# MCU_M_V2.net
KiCad netlist of a schematic drawn in Altium Designer
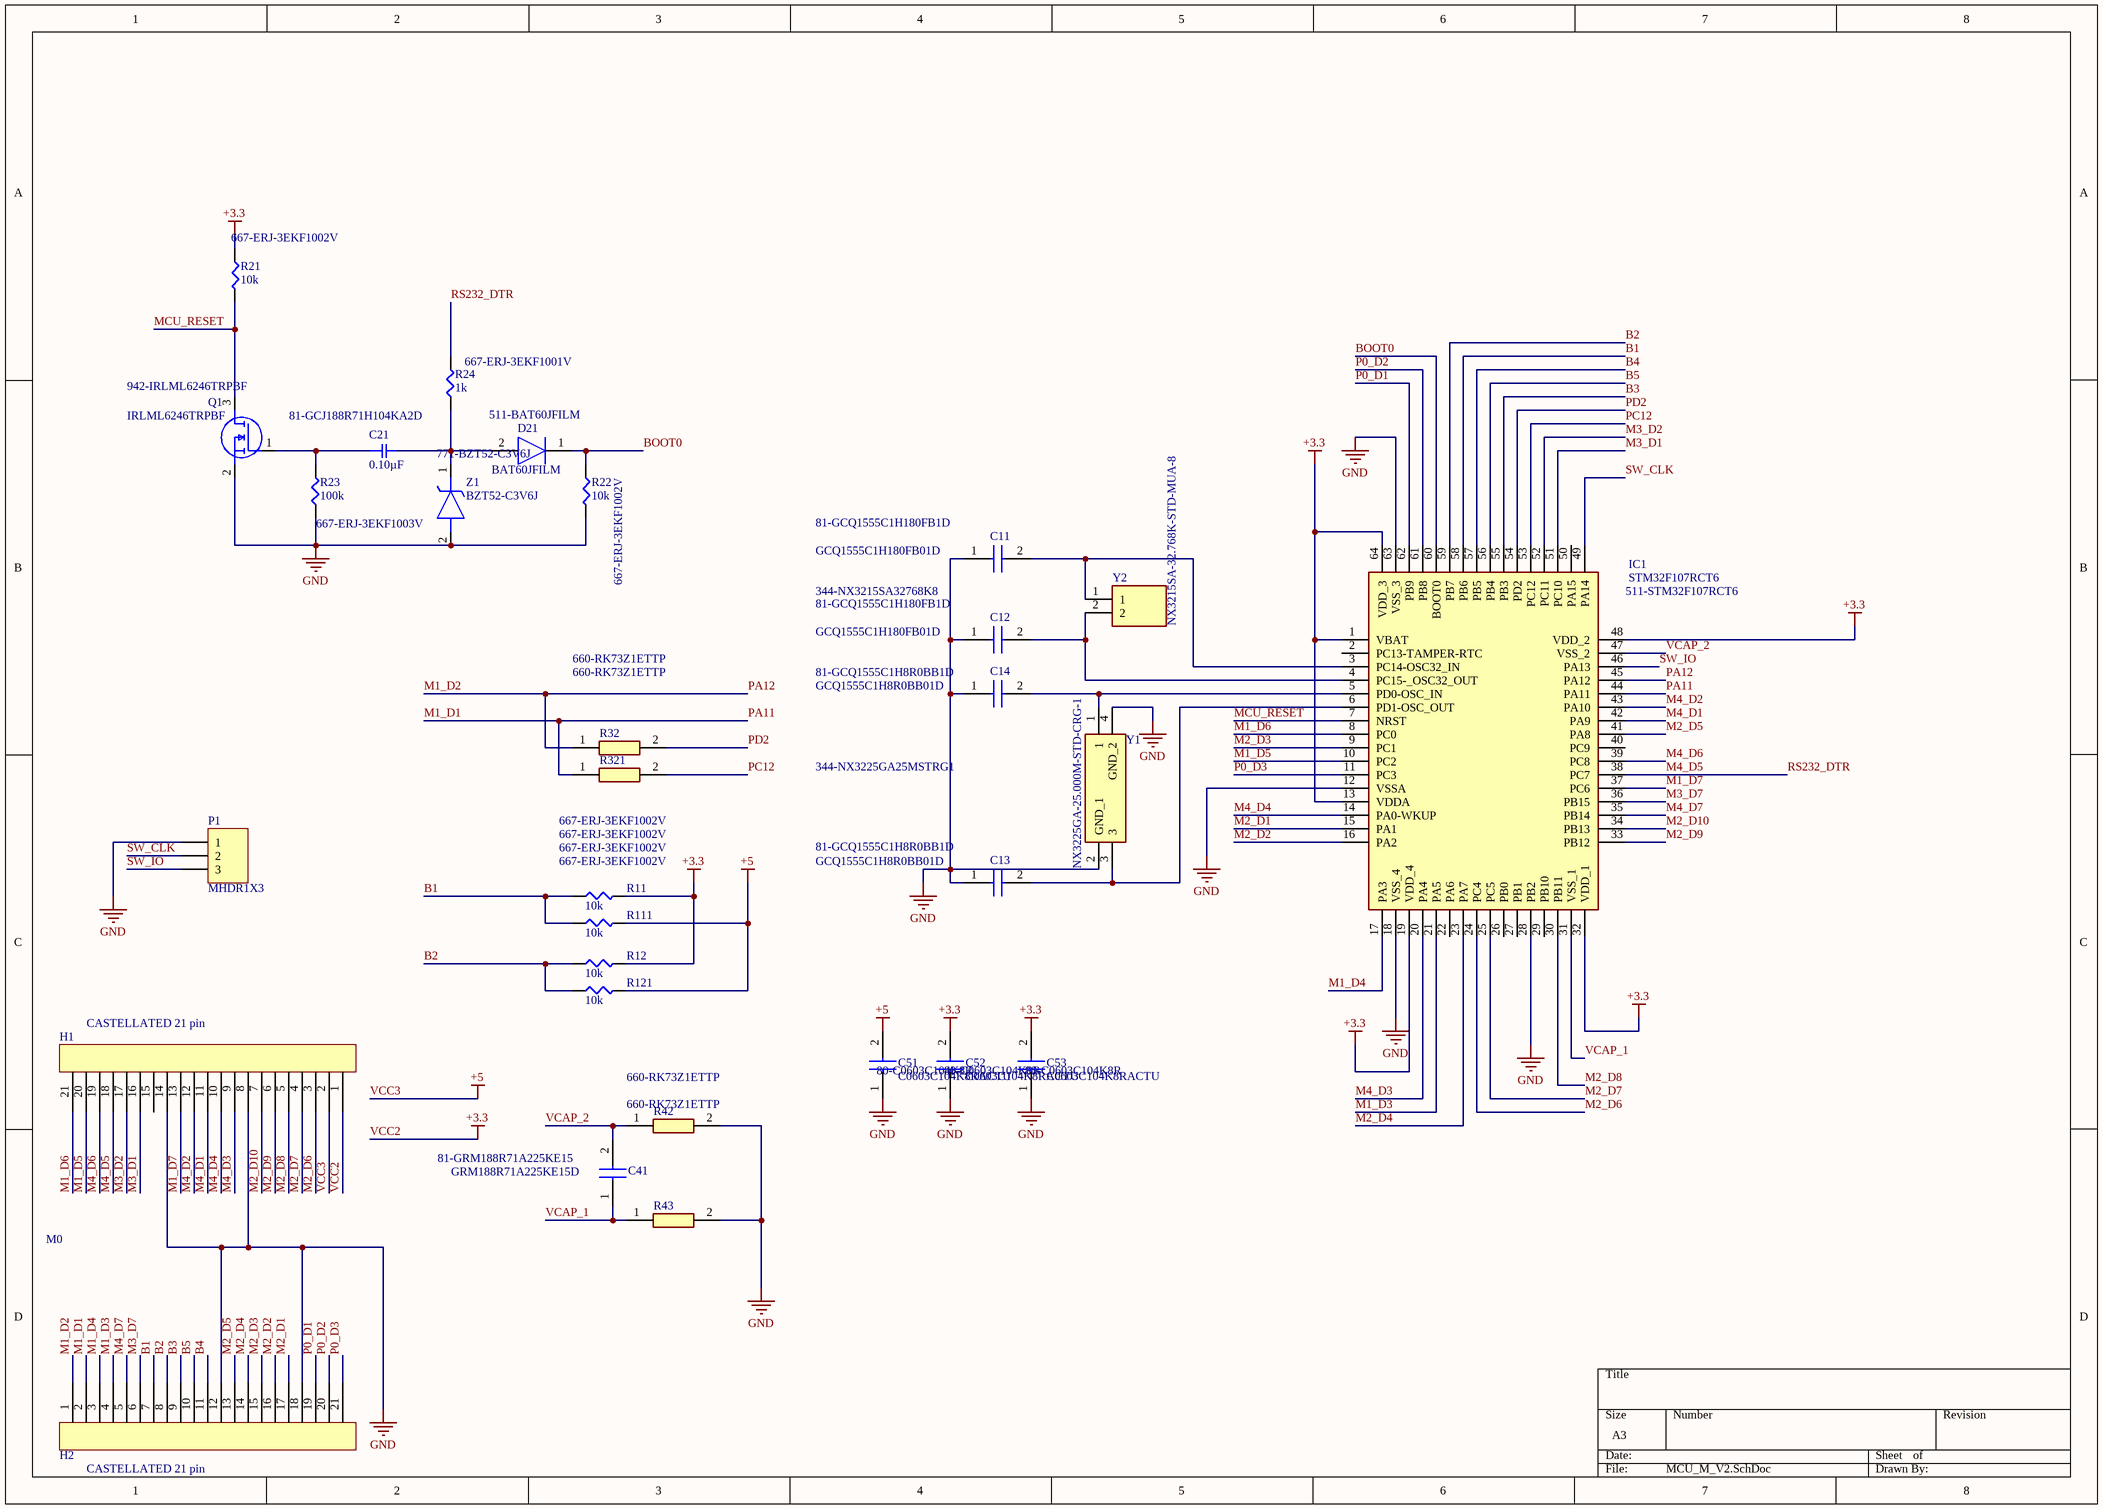
[diagram p0: MCU_M_V2.SchDoc]

(export (version "E")
  (design (tool "Eeschema 10.0.6"))
  (components
    (comp (ref "C11")
      (value "GCQ1555C1H180FB01D")
      (footprint "SamacSys:CAPC1005X55N")
      (description "Capacitor")
      (fields (field (name "SUPPLIER PART NUMBER 1") "81-GCQ1555C1H180FB1D"))
      (libsource (lib "*") (part "GCQ1555C1H180FB01D"))
    )
    (comp (ref "C12")
      (value "GCQ1555C1H180FB01D")
      (footprint "SamacSys:CAPC1005X55N")
      (description "Capacitor")
      (fields (field (name "SUPPLIER PART NUMBER 1") "81-GCQ1555C1H180FB1D"))
      (libsource (lib "*") (part "GCQ1555C1H180FB01D"))
    )
    (comp (ref "C13")
      (value "GCQ1555C1H8R0BB01D")
      (footprint "SamacSys:CAPC1005X55N")
      (description "Capacitor")
      (fields (field (name "SUPPLIER PART NUMBER 1") "81-GCQ1555C1H8R0BB1D"))
      (libsource (lib "*") (part "GCQ1555C1H8R0BB01D"))
    )
    (comp (ref "C14")
      (value "GCQ1555C1H8R0BB01D")
      (footprint "SamacSys:CAPC1005X55N")
      (description "Capacitor")
      (fields (field (name "SUPPLIER PART NUMBER 1") "81-GCQ1555C1H8R0BB1D"))
      (libsource (lib "*") (part "GCQ1555C1H8R0BB01D"))
    )
    (comp (ref "C21")
      (value "0.10µF")
      (footprint "SMD-0603C")
      (description "CAP CER 0.1UF 50V X7R 0603")
      (fields
        (field (name "DIGI-KEY PART NUMBER") "490-5798-1-ND")
        (field (name "PART NUMBER") "GCJ188R71H104KA12D")
        (field (name "SUPPLIER PART NUMBER 1") "81-GCJ188R71H104KA2D")
      )
      (libsource (lib "capacitor_murata_0603") (part "GCJ188R71H104KA12D"))
    )
    (comp (ref "C41")
      (value "GRM188R71A225KE15D")
      (footprint "SamacSys:CAPC1608X90N")
      (description "Capacitor")
      (fields (field (name "SUPPLIER PART NUMBER 1") "81-GRM188R71A225KE15"))
      (libsource (lib "*") (part "GRM188R71A225KE15D"))
    )
    (comp (ref "C51")
      (value "C0603C104K8RACTU")
      (footprint "SamacSys:CAPC1608X90N")
      (description "Capacitor")
      (fields (field (name "SUPPLIER PART NUMBER 1") "80-C0603C104K8R"))
      (libsource (lib "SamacSys") (part "C0603C104K8RACTU"))
    )
    (comp (ref "C52")
      (value "C0603C104K8RACTU")
      (footprint "SamacSys:CAPC1608X90N")
      (description "Capacitor")
      (fields (field (name "SUPPLIER PART NUMBER 1") "80-C0603C104K8R"))
      (libsource (lib "SamacSys") (part "C0603C104K8RACTU"))
    )
    (comp (ref "C53")
      (value "C0603C104K8RACTU")
      (footprint "SamacSys:CAPC1608X90N")
      (description "Capacitor")
      (fields (field (name "SUPPLIER PART NUMBER 1") "80-C0603C104K8R"))
      (libsource (lib "SamacSys") (part "C0603C104K8RACTU"))
    )
    (comp (ref "D21")
      (value "BAT60JFILM")
      (footprint "SamacSys:SOD2513X117N")
      (description "Diode")
      (fields
        (field (name "MOUSER2 PART NUMBER") "511-BAT60JFILM")
        (field (name "SUPPLIER PART NUMBER 1") "511-BAT60JFILM")
      )
      (libsource (lib "*") (part "BAT60JFILM"))
    )
    (comp (ref "H1")
      (value "CASTELLATED 21 pin")
      (footprint "CASTELLATED 21 pin")
      (libsource (lib "USIB") (part "CASTELLATED 21 pin"))
    )
    (comp (ref "H2")
      (value "CASTELLATED 21 pin")
      (footprint "CASTELLATED 21 pin")
      (libsource (lib "") (part "CASTELLATED 21 pin_1"))
    )
    (comp (ref "IC1")
      (value "STM32F107RCT6")
      (footprint "SamacSys:QFP50P1200X1200X160-64N")
      (description "Integrated Circuit")
      (fields
        (field (name "MOUSER2 PART NUMBER") "511-STM32F107RCT6")
        (field (name "SUPPLIER PART NUMBER 1") "511-STM32F107RCT6")
      )
      (libsource (lib "*") (part "STM32F107RCT6"))
    )
    (comp (ref "P1")
      (value "MHDR1X3")
      (footprint "MHDR1X3")
      (description "Header, 3-Pin")
      (fields (field (name "PUBLISHER") "Altium Limited"))
      (libsource (lib "Miscellaneous Connectors") (part "MHDR1X3"))
    )
    (comp (ref "Q1")
      (value "IRLML6246TRPBF")
      (footprint "SamacSys:SOT95P237X112-3N")
      (description "MOSFET (N-Channel)")
      (fields (field (name "SUPPLIER PART NUMBER 1") "942-IRLML6246TRPBF"))
      (libsource (lib "*") (part "IRLML6246TRPBF"))
    )
    (comp (ref "R11")
      (value "10k")
      (footprint "SMD-0603-RES")
      (description "RES SMD 10K OHM 1% 1/10W 0603")
      (fields
        (field (name "PART NUMBER") "ERJ-3EKF1002V")
        (field (name "DIGI-KEY PART NUMBER") "P10.0KHCT-ND")
        (field (name "SUPPLIER PART NUMBER 1") "667-ERJ-3EKF1002V")
      )
      (libsource (lib "Panasonic_ERJ_0603") (part "ERJ-3EKF1002V"))
    )
    (comp (ref "R12")
      (value "10k")
      (footprint "SMD-0603-RES")
      (description "RES SMD 10K OHM 1% 1/10W 0603")
      (fields
        (field (name "PART NUMBER") "ERJ-3EKF1002V")
        (field (name "DIGI-KEY PART NUMBER") "P10.0KHCT-ND")
        (field (name "SUPPLIER PART NUMBER 1") "667-ERJ-3EKF1002V")
      )
      (libsource (lib "Panasonic_ERJ_0603") (part "ERJ-3EKF1002V"))
    )
    (comp (ref "R21")
      (value "10k")
      (footprint "SMD-0603-RES")
      (description "RES SMD 10K OHM 1% 1/10W 0603")
      (fields
        (field (name "PART NUMBER") "ERJ-3EKF1002V")
        (field (name "DIGI-KEY PART NUMBER") "P10.0KHCT-ND")
        (field (name "SUPPLIER PART NUMBER 1") "667-ERJ-3EKF1002V")
      )
      (libsource (lib "Panasonic_ERJ_0603") (part "ERJ-3EKF1002V"))
    )
    (comp (ref "R22")
      (value "10k")
      (footprint "SMD-0603-RES")
      (description "RES SMD 10K OHM 1% 1/10W 0603")
      (fields
        (field (name "PART NUMBER") "ERJ-3EKF1002V")
        (field (name "DIGI-KEY PART NUMBER") "P10.0KHCT-ND")
        (field (name "SUPPLIER PART NUMBER 1") "667-ERJ-3EKF1002V")
      )
      (libsource (lib "Panasonic_ERJ_0603") (part "ERJ-3EKF1002V"))
    )
    (comp (ref "R23")
      (value "100k")
      (footprint "SMD-0603-RES")
      (description "RES SMD 100K OHM 1% 1/10W 0603")
      (fields
        (field (name "PART NUMBER") "ERJ-3EKF1003V")
        (field (name "DIGI-KEY PART NUMBER") "P100KHCT-ND")
        (field (name "SUPPLIER PART NUMBER 1") "667-ERJ-3EKF1003V")
      )
      (libsource (lib "Panasonic_ERJ_0603") (part "ERJ-3EKF1003V"))
    )
    (comp (ref "R24")
      (value "1k")
      (footprint "SMD-0603-RES")
      (description "RES SMD 1K OHM 1% 1/10W 0603")
      (fields
        (field (name "PART NUMBER") "ERJ-3EKF1001V")
        (field (name "DIGI-KEY PART NUMBER") "P1.00KHCT-ND")
        (field (name "SUPPLIER PART NUMBER 1") "667-ERJ-3EKF1001V")
      )
      (libsource (lib "Panasonic_ERJ_0603") (part "ERJ-3EKF1001V"))
    )
    (comp (ref "R32")
      (value "RK73Z1ETTP")
      (footprint "SamacSys:RESC1005X40N")
      (description "Resistor")
      (fields (field (name "SUPPLIER PART NUMBER 1") "660-RK73Z1ETTP"))
      (libsource (lib "SamacSys") (part "RK73Z1ETTP"))
    )
    (comp (ref "R42")
      (value "RK73Z1ETTP")
      (footprint "SamacSys:RESC1005X40N")
      (description "Resistor")
      (fields (field (name "SUPPLIER PART NUMBER 1") "660-RK73Z1ETTP"))
      (libsource (lib "SamacSys") (part "RK73Z1ETTP"))
    )
    (comp (ref "R43")
      (value "RK73Z1ETTP")
      (footprint "SamacSys:RESC1005X40N")
      (description "Resistor")
      (fields (field (name "SUPPLIER PART NUMBER 1") "660-RK73Z1ETTP"))
      (libsource (lib "SamacSys") (part "RK73Z1ETTP"))
    )
    (comp (ref "R111")
      (value "10k")
      (footprint "SMD-0603-RES")
      (description "RES SMD 10K OHM 1% 1/10W 0603")
      (fields
        (field (name "PART NUMBER") "ERJ-3EKF1002V")
        (field (name "DIGI-KEY PART NUMBER") "P10.0KHCT-ND")
        (field (name "SUPPLIER PART NUMBER 1") "667-ERJ-3EKF1002V")
      )
      (libsource (lib "Panasonic_ERJ_0603") (part "ERJ-3EKF1002V"))
    )
    (comp (ref "R121")
      (value "10k")
      (footprint "SMD-0603-RES")
      (description "RES SMD 10K OHM 1% 1/10W 0603")
      (fields
        (field (name "PART NUMBER") "ERJ-3EKF1002V")
        (field (name "DIGI-KEY PART NUMBER") "P10.0KHCT-ND")
        (field (name "SUPPLIER PART NUMBER 1") "667-ERJ-3EKF1002V")
      )
      (libsource (lib "Panasonic_ERJ_0603") (part "ERJ-3EKF1002V"))
    )
    (comp (ref "R321")
      (value "RK73Z1ETTP")
      (footprint "SamacSys:RESC1005X40N")
      (description "Resistor")
      (fields (field (name "SUPPLIER PART NUMBER 1") "660-RK73Z1ETTP"))
      (libsource (lib "SamacSys") (part "RK73Z1ETTP"))
    )
    (comp (ref "Y1")
      (value "NX3225GA-25.000M-STD-CRG-1")
      (footprint "SamacSys:NX3225SA_1")
      (description "Crystal or Oscillator")
      (fields
        (field (name "MOUSER2 PART NUMBER") "344-NX3225GA25MSTRG1")
        (field (name "SUPPLIER PART NUMBER 1") "344-NX3225GA25MSTRG1")
      )
      (libsource (lib "*") (part "NX3225GA-25.000M-STD-CRG-1"))
    )
    (comp (ref "Y2")
      (value "NX3215SA-32.768K-STD-MUA-8")
      (footprint "SamacSys:NX3215SA")
      (description "Crystal or Oscillator")
      (fields
        (field (name "MOUSER2 PART NUMBER") "344-NX3215SA32768K8")
        (field (name "SUPPLIER PART NUMBER 1") "344-NX3215SA32768K8")
      )
      (libsource (lib "*") (part "NX3215SA-32.768K-STD-MUA-8"))
    )
    (comp (ref "Z1")
      (value "BZT52-C3V6J")
      (footprint "SamacSys:SOD123")
      (description "Zener Diode")
      (fields
        (field (name "MOUSER2 PART NUMBER") "771-BZT52-C3V6J")
        (field (name "SUPPLIER PART NUMBER 1") "771-BZT52-C3V6J")
      )
      (libsource (lib "*") (part "BZT52-C3V6J"))
    )
  )
  (nets
    (net (code "1") (name "+3.3") (class "Default")
      (node (ref "C52") (pin "2") (pinfunction "2_2") (pintype "passive"))
      (node (ref "C53") (pin "2") (pinfunction "2_2") (pintype "passive"))
      (node (ref "H1") (pin "1") (pintype "passive"))
      (node (ref "IC1") (pin "1") (pinfunction "VBAT_1") (pintype "passive"))
      (node (ref "IC1") (pin "13") (pinfunction "VDDA_13") (pintype "passive"))
      (node (ref "IC1") (pin "19") (pinfunction "VDD_4_19") (pintype "passive"))
      (node (ref "IC1") (pin "32") (pinfunction "VDD_1_32") (pintype "passive"))
      (node (ref "IC1") (pin "48") (pinfunction "VDD_2_48") (pintype "passive"))
      (node (ref "IC1") (pin "64") (pinfunction "VDD_3_64") (pintype "passive"))
      (node (ref "R11") (pin "2") (pinfunction "2_2") (pintype "passive"))
      (node (ref "R12") (pin "2") (pinfunction "2_2") (pintype "passive"))
      (node (ref "R21") (pin "1") (pinfunction "1_1") (pintype "passive"))
    )
    (net (code "2") (name "+5") (class "Default")
      (node (ref "C51") (pin "2") (pinfunction "2_2") (pintype "passive"))
      (node (ref "H1") (pin "2") (pintype "passive"))
      (node (ref "R111") (pin "2") (pinfunction "2_2") (pintype "passive"))
      (node (ref "R121") (pin "2") (pinfunction "2_2") (pintype "passive"))
    )
    (net (code "3") (name "/B1") (class "Default")
      (node (ref "H2") (pin "7") (pintype "passive"))
      (node (ref "IC1") (pin "58") (pinfunction "PB6_58") (pintype "passive"))
      (node (ref "R11") (pin "1") (pinfunction "1_1") (pintype "passive"))
      (node (ref "R111") (pin "1") (pinfunction "1_1") (pintype "passive"))
    )
    (net (code "4") (name "/B2") (class "Default")
      (node (ref "H2") (pin "8") (pintype "passive"))
      (node (ref "IC1") (pin "59") (pinfunction "PB7_59") (pintype "passive"))
      (node (ref "R12") (pin "1") (pinfunction "1_1") (pintype "passive"))
      (node (ref "R121") (pin "1") (pinfunction "1_1") (pintype "passive"))
    )
    (net (code "5") (name "/B3") (class "Default")
      (node (ref "H2") (pin "9") (pintype "passive"))
      (node (ref "IC1") (pin "55") (pinfunction "PB3_55") (pintype "passive"))
    )
    (net (code "6") (name "/B4") (class "Default")
      (node (ref "H2") (pin "11") (pintype "passive"))
      (node (ref "IC1") (pin "57") (pinfunction "PB5_57") (pintype "passive"))
    )
    (net (code "7") (name "/B5") (class "Default")
      (node (ref "H2") (pin "10") (pintype "passive"))
      (node (ref "IC1") (pin "56") (pinfunction "PB4_56") (pintype "passive"))
    )
    (net (code "8") (name "/BOOT0") (class "Default")
      (node (ref "D21") (pin "1") (pinfunction "K_1") (pintype "passive"))
      (node (ref "IC1") (pin "60") (pinfunction "BOOT0_60") (pintype "passive"))
      (node (ref "R22") (pin "1") (pinfunction "1_1") (pintype "passive"))
    )
    (net (code "9") (name "/M1_D1") (class "Default")
      (node (ref "H2") (pin "2") (pintype "passive"))
      (node (ref "IC1") (pin "44") (pinfunction "PA11_44") (pintype "passive"))
      (node (ref "R321") (pin "1") (pinfunction "1_1") (pintype "passive"))
    )
    (net (code "10") (name "/M1_D2") (class "Default")
      (node (ref "H2") (pin "1") (pintype "passive"))
      (node (ref "IC1") (pin "45") (pinfunction "PA12_45") (pintype "passive"))
      (node (ref "R32") (pin "1") (pinfunction "1_1") (pintype "passive"))
    )
    (net (code "11") (name "/M1_D3") (class "Default")
      (node (ref "H2") (pin "4") (pintype "passive"))
      (node (ref "IC1") (pin "21") (pinfunction "PA5_21") (pintype "passive"))
    )
    (net (code "12") (name "/M1_D4") (class "Default")
      (node (ref "H2") (pin "3") (pintype "passive"))
      (node (ref "IC1") (pin "17") (pinfunction "PA3_17") (pintype "passive"))
    )
    (net (code "13") (name "/M1_D5") (class "Default")
      (node (ref "H1") (pin "20") (pintype "passive"))
      (node (ref "IC1") (pin "10") (pinfunction "PC2_10") (pintype "passive"))
    )
    (net (code "14") (name "/M1_D6") (class "Default")
      (node (ref "H1") (pin "21") (pintype "passive"))
      (node (ref "IC1") (pin "8") (pinfunction "PC0_8") (pintype "passive"))
    )
    (net (code "15") (name "/M1_D7") (class "Default")
      (node (ref "H1") (pin "13") (pintype "passive"))
      (node (ref "IC1") (pin "37") (pinfunction "PC6_37") (pintype "passive"))
    )
    (net (code "16") (name "/M2_D1") (class "Default")
      (node (ref "H2") (pin "17") (pintype "passive"))
      (node (ref "IC1") (pin "15") (pinfunction "PA1_15") (pintype "passive"))
    )
    (net (code "17") (name "/M2_D2") (class "Default")
      (node (ref "H2") (pin "16") (pintype "passive"))
      (node (ref "IC1") (pin "16") (pinfunction "PA2_16") (pintype "passive"))
    )
    (net (code "18") (name "/M2_D3") (class "Default")
      (node (ref "H2") (pin "15") (pintype "passive"))
      (node (ref "IC1") (pin "9") (pinfunction "PC1_9") (pintype "passive"))
    )
    (net (code "19") (name "/M2_D4") (class "Default")
      (node (ref "H2") (pin "14") (pintype "passive"))
      (node (ref "IC1") (pin "23") (pinfunction "PA7_23") (pintype "passive"))
    )
    (net (code "20") (name "/M2_D5") (class "Default")
      (node (ref "H2") (pin "13") (pintype "passive"))
      (node (ref "IC1") (pin "41") (pinfunction "PA8_41") (pintype "passive"))
    )
    (net (code "21") (name "/M2_D6") (class "Default")
      (node (ref "H1") (pin "3") (pintype "passive"))
      (node (ref "IC1") (pin "24") (pinfunction "PC4_24") (pintype "passive"))
    )
    (net (code "22") (name "/M2_D7") (class "Default")
      (node (ref "H1") (pin "4") (pintype "passive"))
      (node (ref "IC1") (pin "25") (pinfunction "PC5_25") (pintype "passive"))
    )
    (net (code "23") (name "/M2_D8") (class "Default")
      (node (ref "H1") (pin "5") (pintype "passive"))
      (node (ref "IC1") (pin "30") (pinfunction "PB11_30") (pintype "passive"))
    )
    (net (code "24") (name "/M2_D9") (class "Default")
      (node (ref "H1") (pin "6") (pintype "passive"))
      (node (ref "IC1") (pin "33") (pinfunction "PB12_33") (pintype "passive"))
    )
    (net (code "25") (name "/M2_D10") (class "Default")
      (node (ref "H1") (pin "7") (pintype "passive"))
      (node (ref "IC1") (pin "34") (pinfunction "PB13_34") (pintype "passive"))
    )
    (net (code "26") (name "/M3_D1") (class "Default")
      (node (ref "H1") (pin "16") (pintype "passive"))
      (node (ref "IC1") (pin "51") (pinfunction "PC10_51") (pintype "passive"))
    )
    (net (code "27") (name "/M3_D2") (class "Default")
      (node (ref "H1") (pin "17") (pintype "passive"))
      (node (ref "IC1") (pin "52") (pinfunction "PC11_52") (pintype "passive"))
    )
    (net (code "28") (name "/M3_D7") (class "Default")
      (node (ref "H2") (pin "6") (pintype "passive"))
      (node (ref "IC1") (pin "36") (pinfunction "PB15_36") (pintype "passive"))
    )
    (net (code "29") (name "/M4_D1") (class "Default")
      (node (ref "H1") (pin "11") (pintype "passive"))
      (node (ref "IC1") (pin "42") (pinfunction "PA9_42") (pintype "passive"))
    )
    (net (code "30") (name "/M4_D2") (class "Default")
      (node (ref "H1") (pin "12") (pintype "passive"))
      (node (ref "IC1") (pin "43") (pinfunction "PA10_43") (pintype "passive"))
    )
    (net (code "31") (name "/M4_D3") (class "Default")
      (node (ref "H1") (pin "9") (pintype "passive"))
      (node (ref "IC1") (pin "20") (pinfunction "PA4_20") (pintype "passive"))
    )
    (net (code "32") (name "/M4_D4") (class "Default")
      (node (ref "H1") (pin "10") (pintype "passive"))
      (node (ref "IC1") (pin "14") (pinfunction "PA0-WKUP_14") (pintype "passive"))
    )
    (net (code "33") (name "/M4_D5") (class "Default")
      (node (ref "H1") (pin "18") (pintype "passive"))
      (node (ref "IC1") (pin "38") (pinfunction "PC7_38") (pintype "passive"))
      (node (ref "R24") (pin "2") (pinfunction "2_2") (pintype "passive"))
    )
    (net (code "34") (name "/M4_D6") (class "Default")
      (node (ref "H1") (pin "19") (pintype "passive"))
      (node (ref "IC1") (pin "39") (pinfunction "PC8_39") (pintype "passive"))
    )
    (net (code "35") (name "/M4_D7") (class "Default")
      (node (ref "H2") (pin "5") (pintype "passive"))
      (node (ref "IC1") (pin "35") (pinfunction "PB14_35") (pintype "passive"))
    )
    (net (code "36") (name "/MCU_RESET") (class "Default")
      (node (ref "IC1") (pin "7") (pinfunction "NRST_7") (pintype "passive"))
      (node (ref "Q1") (pin "3") (pinfunction "D_3") (pintype "passive"))
      (node (ref "R21") (pin "2") (pinfunction "2_2") (pintype "passive"))
    )
    (net (code "37") (name "/P0_D1") (class "Default")
      (node (ref "H2") (pin "19") (pintype "passive"))
      (node (ref "IC1") (pin "62") (pinfunction "PB9_62") (pintype "passive"))
    )
    (net (code "38") (name "/P0_D2") (class "Default")
      (node (ref "H2") (pin "20") (pintype "passive"))
      (node (ref "IC1") (pin "61") (pinfunction "PB8_61") (pintype "passive"))
    )
    (net (code "39") (name "/P0_D3") (class "Default")
      (node (ref "H2") (pin "21") (pintype "passive"))
      (node (ref "IC1") (pin "11") (pinfunction "PC3_11") (pintype "passive"))
    )
    (net (code "40") (name "/PC12") (class "Default")
      (node (ref "IC1") (pin "53") (pinfunction "PC12_53") (pintype "passive"))
      (node (ref "R321") (pin "2") (pinfunction "2_2") (pintype "passive"))
    )
    (net (code "41") (name "/PD2") (class "Default")
      (node (ref "IC1") (pin "54") (pinfunction "PD2_54") (pintype "passive"))
      (node (ref "R32") (pin "2") (pinfunction "2_2") (pintype "passive"))
    )
    (net (code "42") (name "/SW_CLK") (class "Default")
      (node (ref "IC1") (pin "49") (pinfunction "PA14_49") (pintype "passive"))
      (node (ref "P1") (pin "2") (pinfunction "2_2") (pintype "passive"))
    )
    (net (code "43") (name "/SW_IO") (class "Default")
      (node (ref "IC1") (pin "46") (pinfunction "PA13_46") (pintype "passive"))
      (node (ref "P1") (pin "3") (pinfunction "3_3") (pintype "passive"))
    )
    (net (code "44") (name "/VCAP_1") (class "Default")
      (node (ref "C41") (pin "1") (pinfunction "1_1") (pintype "passive"))
      (node (ref "IC1") (pin "31") (pinfunction "VSS_1_31") (pintype "passive"))
      (node (ref "R43") (pin "1") (pinfunction "1_1") (pintype "passive"))
    )
    (net (code "45") (name "/VCAP_2") (class "Default")
      (node (ref "C41") (pin "2") (pinfunction "2_2") (pintype "passive"))
      (node (ref "IC1") (pin "47") (pinfunction "VSS_2_47") (pintype "passive"))
      (node (ref "R42") (pin "1") (pinfunction "1_1") (pintype "passive"))
    )
    (net (code "46") (name "GND") (class "Default")
      (node (ref "C11") (pin "1") (pinfunction "1_1") (pintype "passive"))
      (node (ref "C12") (pin "1") (pinfunction "1_1") (pintype "passive"))
      (node (ref "C13") (pin "1") (pinfunction "1_1") (pintype "passive"))
      (node (ref "C14") (pin "1") (pinfunction "1_1") (pintype "passive"))
      (node (ref "C51") (pin "1") (pinfunction "1_1") (pintype "passive"))
      (node (ref "C52") (pin "1") (pinfunction "1_1") (pintype "passive"))
      (node (ref "C53") (pin "1") (pinfunction "1_1") (pintype "passive"))
      (node (ref "H1") (pin "14") (pintype "passive"))
      (node (ref "H1") (pin "8") (pintype "passive"))
      (node (ref "H2") (pin "12") (pintype "passive"))
      (node (ref "H2") (pin "18") (pintype "passive"))
      (node (ref "IC1") (pin "12") (pinfunction "VSSA_12") (pintype "passive"))
      (node (ref "IC1") (pin "18") (pinfunction "VSS_4_18") (pintype "passive"))
      (node (ref "IC1") (pin "28") (pinfunction "PB2_28") (pintype "passive"))
      (node (ref "IC1") (pin "63") (pinfunction "VSS_3_63") (pintype "passive"))
      (node (ref "P1") (pin "1") (pinfunction "1_1") (pintype "passive"))
      (node (ref "Q1") (pin "2") (pinfunction "S_2") (pintype "passive"))
      (node (ref "R22") (pin "2") (pinfunction "2_2") (pintype "passive"))
      (node (ref "R23") (pin "1") (pinfunction "1_1") (pintype "passive"))
      (node (ref "R42") (pin "2") (pinfunction "2_2") (pintype "passive"))
      (node (ref "R43") (pin "2") (pinfunction "2_2") (pintype "passive"))
      (node (ref "Y1") (pin "2") (pinfunction "GND_1_2") (pintype "passive"))
      (node (ref "Y1") (pin "4") (pinfunction "GND_2_4") (pintype "passive"))
      (node (ref "Z1") (pin "2") (pinfunction "A_2") (pintype "passive"))
    )
    (net (code "47") (name "Net-(D21-A)") (class "Default")
      (node (ref "C21") (pin "2") (pinfunction "2_2") (pintype "passive"))
      (node (ref "D21") (pin "2") (pinfunction "A_2") (pintype "passive"))
      (node (ref "R24") (pin "1") (pinfunction "1_1") (pintype "passive"))
      (node (ref "Z1") (pin "1") (pinfunction "K_1") (pintype "passive"))
    )
    (net (code "48") (name "Net-(IC1-PC14-OSC32_IN)") (class "Default")
      (node (ref "C11") (pin "2") (pinfunction "2_2") (pintype "passive"))
      (node (ref "IC1") (pin "3") (pinfunction "PC14-OSC32_IN_3") (pintype "passive"))
      (node (ref "Y2") (pin "1") (pinfunction "1_1") (pintype "passive"))
    )
    (net (code "49") (name "Net-(IC1-PC15-_OSC32_OUT)") (class "Default")
      (node (ref "C12") (pin "2") (pinfunction "2_2") (pintype "passive"))
      (node (ref "IC1") (pin "4") (pinfunction "PC15-_OSC32_OUT_4") (pintype "passive"))
      (node (ref "Y2") (pin "2") (pinfunction "2_2") (pintype "passive"))
    )
    (net (code "50") (name "Net-(IC1-PD0-OSC_IN)") (class "Default")
      (node (ref "C14") (pin "2") (pinfunction "2_2") (pintype "passive"))
      (node (ref "IC1") (pin "5") (pinfunction "PD0-OSC_IN_5") (pintype "passive"))
      (node (ref "Y1") (pin "1") (pinfunction "1_1") (pintype "passive"))
    )
    (net (code "51") (name "Net-(IC1-PD1-OSC_OUT)") (class "Default")
      (node (ref "C13") (pin "2") (pinfunction "2_2") (pintype "passive"))
      (node (ref "IC1") (pin "6") (pinfunction "PD1-OSC_OUT_6") (pintype "passive"))
      (node (ref "Y1") (pin "3") (pinfunction "3_3") (pintype "passive"))
    )
    (net (code "52") (name "Net-(Q1-G)") (class "Default")
      (node (ref "C21") (pin "1") (pinfunction "1_1") (pintype "passive"))
      (node (ref "Q1") (pin "1") (pinfunction "G_1") (pintype "passive"))
      (node (ref "R23") (pin "2") (pinfunction "2_2") (pintype "passive"))
    )
    (net (code "53") (name "unconnected-(H1-Pad15)") (class "Default")
      (node (ref "H1") (pin "15") (pintype "passive"))
    )
    (net (code "54") (name "unconnected-(IC1-PA6-Pad22)") (class "Default")
      (node (ref "IC1") (pin "22") (pinfunction "PA6_22") (pintype "passive"))
    )
    (net (code "55") (name "unconnected-(IC1-PA15-Pad50)") (class "Default")
      (node (ref "IC1") (pin "50") (pinfunction "PA15_50") (pintype "passive"))
    )
    (net (code "56") (name "unconnected-(IC1-PB0-Pad26)") (class "Default")
      (node (ref "IC1") (pin "26") (pinfunction "PB0_26") (pintype "passive"))
    )
    (net (code "57") (name "unconnected-(IC1-PB1-Pad27)") (class "Default")
      (node (ref "IC1") (pin "27") (pinfunction "PB1_27") (pintype "passive"))
    )
    (net (code "58") (name "unconnected-(IC1-PB10-Pad29)") (class "Default")
      (node (ref "IC1") (pin "29") (pinfunction "PB10_29") (pintype "passive"))
    )
    (net (code "59") (name "unconnected-(IC1-PC9-Pad40)") (class "Default")
      (node (ref "IC1") (pin "40") (pinfunction "PC9_40") (pintype "passive"))
    )
    (net (code "60") (name "unconnected-(IC1-PC13-TAMPER-RTC-Pad2)") (class "Default")
      (node (ref "IC1") (pin "2") (pinfunction "PC13-TAMPER-RTC_2") (pintype "passive"))
    )
  )
)
